# Power.net
KiCad netlist of a schematic drawn in Altium Designer
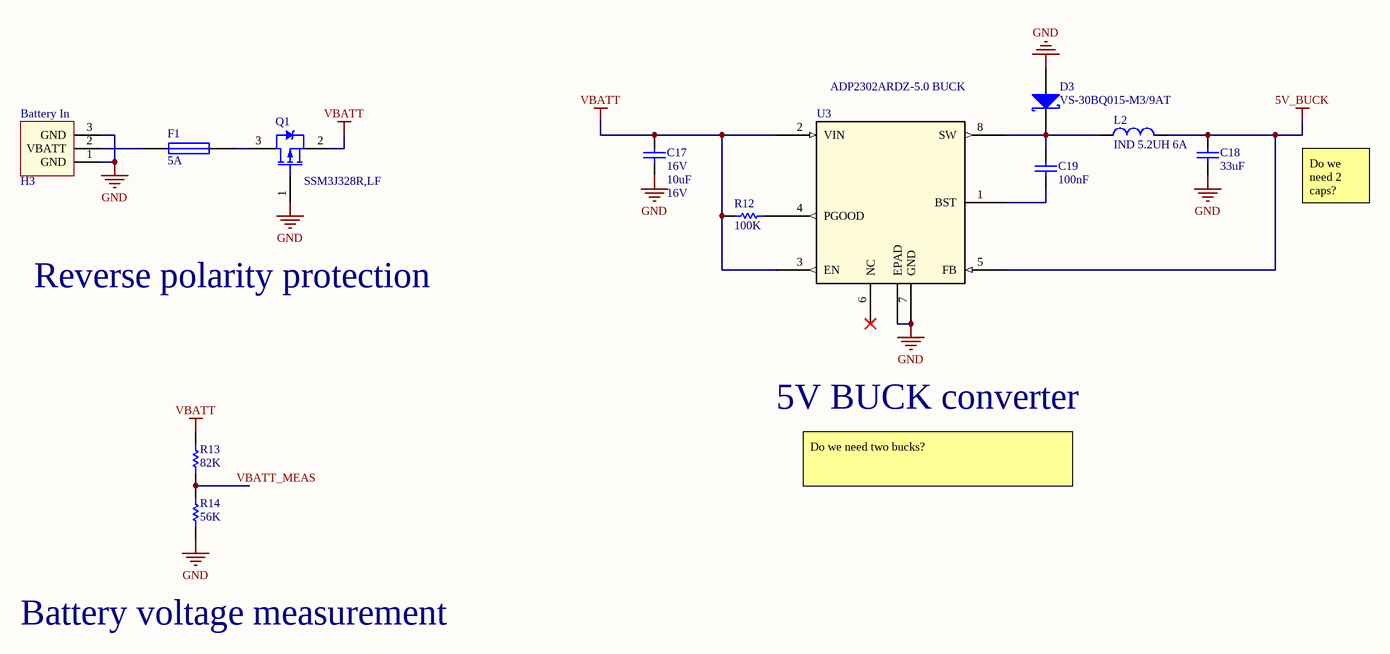
[diagram p0: Power.SchDoc]

(export (version "E")
  (design (tool "Eeschema 10.0.6"))
  (components
    (comp (ref "C17")
      (value "10uF")
      (footprint "CAPC2012L")
      (description "CAP CER 10uF X5R 16V 0805")
      (fields
        (field (name "MANUFACTURER") "Samsung Electro-Mechanics")
        (field (name "MANUFACTURER PART NUMBER") "CL21A106KOQNNWE")
        (field (name "VOLTAGE - RATED") "16V")
        (field (name "MAX VOLTAGE") "16V")
      )
      (libsource (lib "ENCE461AD19_19V2") (part "CC_10uF_16V_0805"))
    )
    (comp (ref "C18")
      (value "33uF")
      (footprint "CAPC2012L")
      (description "CAP CER 33uF X5R 6V3 0805")
      (fields
        (field (name "MANUFACTURER") "TDK Corporation")
        (field (name "MANUFACTURER PART NUMBER") "C2012X5R0J336M125AC")
      )
      (libsource (lib "ENCE461AD19_19V2") (part "CC_33uF_6V3_0805"))
    )
    (comp (ref "C19")
      (value "100nF")
      (footprint "CAPC1608L")
      (description "CAP CER 100nF X7R +-10% 50V 0603")
      (libsource (lib "ECE AD19Components_19V1") (part "CC_100nF_0603"))
    )
    (comp (ref "D3")
      (value "VS-30BQ015-M3/9AT")
      (footprint "SMC")
      (description "DIODE, SCHOTTKY, 3A, 15V, DO-214AB / SMC")
      (fields (field (name "MANUFACTURER") "Vishay Semiconductors"))
      (libsource (lib "ECE AD19Components_19V1") (part "DS_VS-30BQ015-M3"))
    )
    (comp (ref "F1")
      (value "5A")
      (footprint "RESC3216N")
      (description "Fuse 5.0A Fast Acting 1206 SMD")
      (fields (field (name "MANUFACTURER PART NUMBER") "C1F5") (field (name "MANUFACTURER") "Bel TRP"))
      (libsource (lib "ECE AD19Components_19V1") (part "FS_Fuse_5.0A"))
    )
    (comp (ref "H3")
      (value "Battery In")
      (footprint "BATT_HEADER_3POS")
      (description "3Pin Header 2.54mm spacing")
      (libsource (lib "ENCE461AD19_19V2") (part "Battery_HEADER_3pin"))
    )
    (comp (ref "L2")
      (value "IND 5.2UH 6A")
      (footprint "INDUCTOR5u2")
      (description "FIXED IND 5.2UH 6A 22 MOHM SMD")
      (fields
        (field (name "MANUFACTURER") "Sumida America Components Inc.")
        (field (name "MANUFACTURER PART NUMBER") "CDRH104RNP-5R2NC")
      )
      (libsource (lib "ENCE461AD19_19V2") (part "CDRH104RNP-5R2NC"))
    )
    (comp (ref "Q1")
      (value "SSM3J328R,LF")
      (footprint "SOT23_L")
      (description "MOSFET P-CH 20V 6A SOT23-3")
      (fields
        (field (name "MANUFACTURER") "Toshiba")
        (field (name "MANUFACTURER PART NUMBER") "SSM3J328R,LF")
      )
      (libsource (lib "ECE AD19Components_19V1") (part "TM_SSM3J328R"))
    )
    (comp (ref "R12")
      (value "100K")
      (footprint "RESC1608L")
      (description "RES 100K OHM 1/10W 5% 0603 SMD")
      (libsource (lib "ECE AD19Components_19V1") (part "RS_100K"))
    )
    (comp (ref "R13")
      (value "82K")
      (footprint "RESC1608L")
      (description "RES 82.0K OHM 1/10W 5% 0603 SMD")
      (libsource (lib "ECE AD19Components_19V1") (part "RS_82K"))
    )
    (comp (ref "R14")
      (value "56K")
      (footprint "RESC1608L")
      (description "RES 56.0K OHM 1/10W 5% 0603 SMD")
      (libsource (lib "ECE AD19Components_19V1") (part "RS_56K"))
    )
    (comp (ref "U3")
      (value "ADP2302ARDZ-5.0 BUCK")
      (footprint "RD_8_1")
      (description "IC REG BUCK 5V 2A 8SOIC")
      (fields (field (name "MANUFACTURER_PART_NUMBER") "ADP2302ARDZ-5.0-R7"))
      (libsource (lib "ENCE461AD19_19V2") (part "ADP2302ARDZ-5.0-R7"))
    )
  )
  (nets
    (net (code "1") (name "/VBATT_MEAS") (class "Default")
      (node (ref "R13") (pin "1") (pinfunction "1_1") (pintype "passive"))
      (node (ref "R14") (pin "2") (pinfunction "2_2") (pintype "passive"))
    )
    (net (code "2") (name "5V_BUCK") (class "Default")
      (node (ref "C18") (pin "2") (pinfunction "2_2") (pintype "passive"))
      (node (ref "L2") (pin "2") (pintype "passive"))
      (node (ref "U3") (pin "5") (pinfunction "FB_5") (pintype "input"))
    )
    (net (code "3") (name "GND") (class "Default")
      (node (ref "C17") (pin "1") (pinfunction "1_1") (pintype "passive"))
      (node (ref "C18") (pin "1") (pinfunction "1_1") (pintype "passive"))
      (node (ref "D3") (pin "1") (pinfunction "A_1") (pintype "passive"))
      (node (ref "H3") (pin "1") (pinfunction "GND_1") (pintype "passive"))
      (node (ref "H3") (pin "3") (pinfunction "GND_3") (pintype "passive"))
      (node (ref "Q1") (pin "1") (pinfunction "1_1") (pintype "passive"))
      (node (ref "R14") (pin "1") (pinfunction "1_1") (pintype "passive"))
      (node (ref "U3") (pin "7") (pinfunction "GND_7") (pintype "power_in"))
      (node (ref "U3") (pin "EPAD") (pinfunction "EPAD_EPAD") (pintype "passive"))
    )
    (net (code "4") (name "Net-(D3-K)") (class "Default")
      (node (ref "C19") (pin "2") (pinfunction "2_2") (pintype "passive"))
      (node (ref "D3") (pin "2") (pinfunction "K_2") (pintype "passive"))
      (node (ref "L2") (pin "1") (pintype "passive"))
      (node (ref "U3") (pin "8") (pinfunction "SW_8") (pintype "output"))
    )
    (net (code "5") (name "Net-(F1-Pad2)") (class "Default")
      (node (ref "F1") (pin "2") (pinfunction "2_2") (pintype "passive"))
      (node (ref "Q1") (pin "3") (pinfunction "3_3") (pintype "passive"))
    )
    (net (code "6") (name "Net-(H3-VBATT)") (class "Default")
      (node (ref "F1") (pin "1") (pinfunction "1_1") (pintype "passive"))
      (node (ref "H3") (pin "2") (pinfunction "VBATT_2") (pintype "passive"))
    )
    (net (code "7") (name "Net-(U3-BST)") (class "Default")
      (node (ref "C19") (pin "1") (pinfunction "1_1") (pintype "passive"))
      (node (ref "U3") (pin "1") (pinfunction "BST_1") (pintype "passive"))
    )
    (net (code "8") (name "Net-(U3-PGOOD)") (class "Default")
      (node (ref "R12") (pin "2") (pinfunction "2_2") (pintype "passive"))
      (node (ref "U3") (pin "4") (pinfunction "PGOOD_4") (pintype "output"))
    )
    (net (code "9") (name "VBATT") (class "Default")
      (node (ref "C17") (pin "2") (pinfunction "2_2") (pintype "passive"))
      (node (ref "Q1") (pin "2") (pinfunction "2_2") (pintype "passive"))
      (node (ref "R12") (pin "1") (pinfunction "1_1") (pintype "passive"))
      (node (ref "R13") (pin "2") (pinfunction "2_2") (pintype "passive"))
      (node (ref "U3") (pin "2") (pinfunction "VIN_2") (pintype "input"))
      (node (ref "U3") (pin "3") (pinfunction "EN_3") (pintype "output"))
    )
    (net (code "10") (name "unconnected-(U3-NC-Pad6)") (class "Default")
      (node (ref "U3") (pin "6") (pinfunction "NC_6") (pintype "passive+no_connect"))
    )
  )
)
